# PROC099A_HD_Connector.net
KiCad netlist of a schematic drawn in Altium Designer
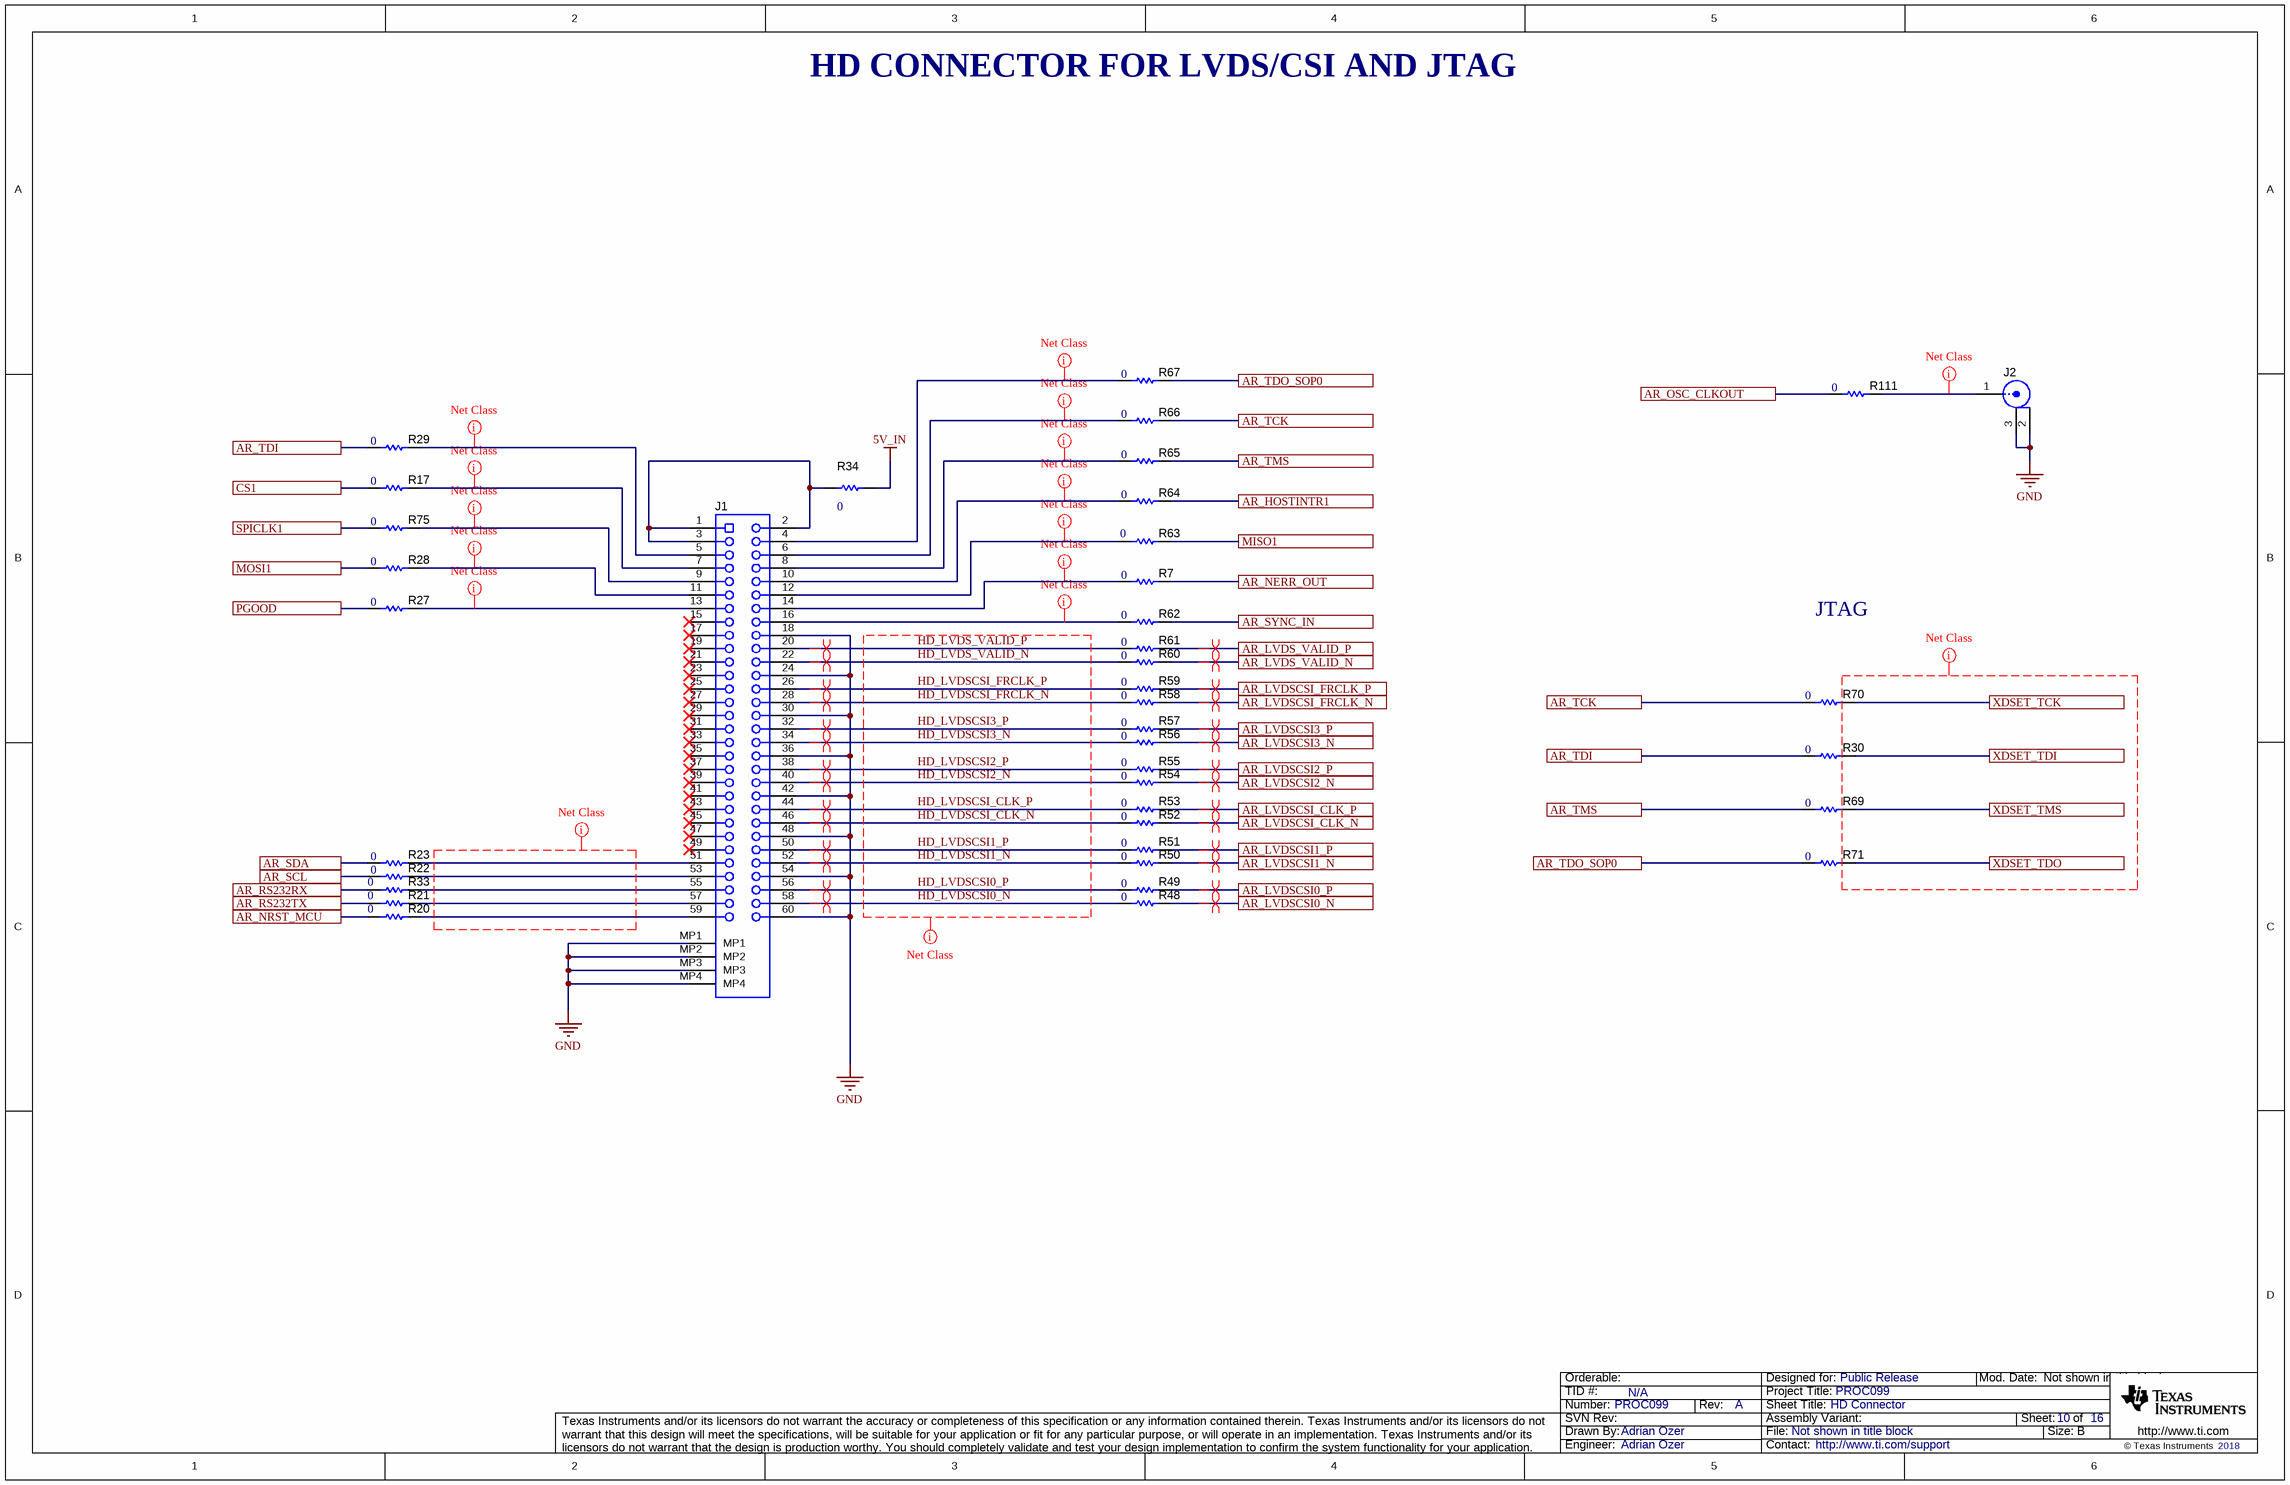
[diagram p0: PROC099A_HD Connector.SchDoc]

(export (version "E")
  (design (tool "Eeschema 10.0.6"))
  (components
    (comp (ref "J1")
      (value "QSH-030-01-L-D-A")
      (footprint "Samtec_QSH-030-01-X-D-A")
      (description "Receptacle, 0.5 mm, 30x2, Gold, TH")
      (fields (field (name "MANUFACTURER") "Samtec") (field (name "PUBLISHER") "Texas Instruments"))
      (libsource (lib "Altium Vault - TI") (part "Receptacle_30x2_4MP_LeftRight"))
    )
    (comp (ref "J2")
      (value "128-0711-201")
      (footprint "Johnson_128-0711-201")
      (description "UMC Straight Jack Receptacle, 50 Ohm, Gold, SMT")
      (fields
        (field (name "MANUFACTURER") "Cinch Connectivity")
        (field (name "PUBLISHER") "Texas Instruments")
      )
      (libsource (lib "Altium Vault - TI") (part "CMP-0055788-1"))
    )
    (comp (ref "R7")
      (value "CRCW02010000Z0ED")
      (footprint "0201_Silk")
      (description "RES, 0, 5%, 0.05 W, 0201")
      (fields (field (name "MANUFACTURER") "Vishay-Dale") (field (name "VALUEDISPLAYED") "0"))
      (libsource (lib "Altium Vault - TI") (part "Resistor"))
    )
    (comp (ref "R17")
      (value "CRCW02010000Z0ED")
      (footprint "0201_Silk")
      (description "RES, 0, 5%, 0.05 W, 0201")
      (fields (field (name "MANUFACTURER") "Vishay-Dale") (field (name "VALUEDISPLAYED") "0"))
      (libsource (lib "Altium Vault - TI") (part "Resistor"))
    )
    (comp (ref "R20")
      (value "CRCW02010000Z0ED")
      (footprint "0201_Silk")
      (description "RES, 0, 5%, 0.05 W, 0201")
      (fields (field (name "MANUFACTURER") "Vishay-Dale") (field (name "VALUEDISPLAYED") "0"))
      (libsource (lib "Altium Vault - TI") (part "Resistor"))
    )
    (comp (ref "R21")
      (value "CRCW02010000Z0ED")
      (footprint "0201_Silk")
      (description "RES, 0, 5%, 0.05 W, 0201")
      (fields (field (name "MANUFACTURER") "Vishay-Dale") (field (name "VALUEDISPLAYED") "0"))
      (libsource (lib "Altium Vault - TI") (part "Resistor"))
    )
    (comp (ref "R22")
      (value "CRCW02010000Z0ED")
      (footprint "0201_Silk")
      (description "RES, 0, 5%, 0.05 W, 0201")
      (fields (field (name "MANUFACTURER") "Vishay-Dale") (field (name "VALUEDISPLAYED") "0"))
      (libsource (lib "Altium Vault - TI") (part "Resistor"))
    )
    (comp (ref "R23")
      (value "CRCW02010000Z0ED")
      (footprint "0201_Silk")
      (description "RES, 0, 5%, 0.05 W, 0201")
      (fields (field (name "MANUFACTURER") "Vishay-Dale") (field (name "VALUEDISPLAYED") "0"))
      (libsource (lib "Altium Vault - TI") (part "Resistor"))
    )
    (comp (ref "R27")
      (value "CRCW02010000Z0ED")
      (footprint "0201_Silk")
      (description "RES, 0, 5%, 0.05 W, 0201")
      (fields (field (name "MANUFACTURER") "Vishay-Dale") (field (name "VALUEDISPLAYED") "0"))
      (libsource (lib "Altium Vault - TI") (part "Resistor"))
    )
    (comp (ref "R28")
      (value "CRCW02010000Z0ED")
      (footprint "0201_Silk")
      (description "RES, 0, 5%, 0.05 W, 0201")
      (fields (field (name "MANUFACTURER") "Vishay-Dale") (field (name "VALUEDISPLAYED") "0"))
      (libsource (lib "Altium Vault - TI") (part "Resistor"))
    )
    (comp (ref "R29")
      (value "CRCW02010000Z0ED")
      (footprint "0201_Silk")
      (description "RES, 0, 5%, 0.05 W, 0201")
      (fields (field (name "MANUFACTURER") "Vishay-Dale") (field (name "VALUEDISPLAYED") "0"))
      (libsource (lib "Altium Vault - TI") (part "Resistor"))
    )
    (comp (ref "R30")
      (value "CRCW02010000Z0ED")
      (footprint "0201_Silk")
      (description "RES, 0, 5%, 0.05 W, 0201")
      (fields (field (name "MANUFACTURER") "Vishay-Dale") (field (name "VALUEDISPLAYED") "0"))
      (libsource (lib "Altium Vault - TI") (part "Resistor"))
    )
    (comp (ref "R33")
      (value "CRCW02010000Z0ED")
      (footprint "0201_Silk")
      (description "RES, 0, 5%, 0.05 W, 0201")
      (fields (field (name "MANUFACTURER") "Vishay-Dale") (field (name "VALUEDISPLAYED") "0"))
      (libsource (lib "Altium Vault - TI") (part "Resistor"))
    )
    (comp (ref "R34")
      (value "CRCW20100000Z0EF")
      (footprint "2010L")
      (description "RES, 0, 5%, 0.75 W, AEC-Q200 Grade 0, 2010")
      (fields (field (name "MANUFACTURER") "Vishay-Dale") (field (name "VALUEDISPLAYED") "0"))
      (libsource (lib "Altium Vault - TI") (part "CMP-0016044-3"))
    )
    (comp (ref "R48")
      (value "CRCW02010000Z0ED")
      (footprint "0201_Silk")
      (description "RES, 0, 5%, 0.05 W, 0201")
      (fields (field (name "MANUFACTURER") "Vishay-Dale") (field (name "VALUEDISPLAYED") "0"))
      (libsource (lib "Altium Vault - TI") (part "Resistor"))
    )
    (comp (ref "R49")
      (value "CRCW02010000Z0ED")
      (footprint "0201_Silk")
      (description "RES, 0, 5%, 0.05 W, 0201")
      (fields (field (name "MANUFACTURER") "Vishay-Dale") (field (name "VALUEDISPLAYED") "0"))
      (libsource (lib "Altium Vault - TI") (part "Resistor"))
    )
    (comp (ref "R50")
      (value "CRCW02010000Z0ED")
      (footprint "0201_Silk")
      (description "RES, 0, 5%, 0.05 W, 0201")
      (fields (field (name "MANUFACTURER") "Vishay-Dale") (field (name "VALUEDISPLAYED") "0"))
      (libsource (lib "Altium Vault - TI") (part "Resistor"))
    )
    (comp (ref "R51")
      (value "CRCW02010000Z0ED")
      (footprint "0201_Silk")
      (description "RES, 0, 5%, 0.05 W, 0201")
      (fields (field (name "MANUFACTURER") "Vishay-Dale") (field (name "VALUEDISPLAYED") "0"))
      (libsource (lib "Altium Vault - TI") (part "Resistor"))
    )
    (comp (ref "R52")
      (value "CRCW02010000Z0ED")
      (footprint "0201_Silk")
      (description "RES, 0, 5%, 0.05 W, 0201")
      (fields (field (name "MANUFACTURER") "Vishay-Dale") (field (name "VALUEDISPLAYED") "0"))
      (libsource (lib "Altium Vault - TI") (part "Resistor"))
    )
    (comp (ref "R53")
      (value "CRCW02010000Z0ED")
      (footprint "0201_Silk")
      (description "RES, 0, 5%, 0.05 W, 0201")
      (fields (field (name "MANUFACTURER") "Vishay-Dale") (field (name "VALUEDISPLAYED") "0"))
      (libsource (lib "Altium Vault - TI") (part "Resistor"))
    )
    (comp (ref "R54")
      (value "CRCW02010000Z0ED")
      (footprint "0201_Silk")
      (description "RES, 0, 5%, 0.05 W, 0201")
      (fields (field (name "MANUFACTURER") "Vishay-Dale") (field (name "VALUEDISPLAYED") "0"))
      (libsource (lib "Altium Vault - TI") (part "Resistor"))
    )
    (comp (ref "R55")
      (value "CRCW02010000Z0ED")
      (footprint "0201_Silk")
      (description "RES, 0, 5%, 0.05 W, 0201")
      (fields (field (name "MANUFACTURER") "Vishay-Dale") (field (name "VALUEDISPLAYED") "0"))
      (libsource (lib "Altium Vault - TI") (part "Resistor"))
    )
    (comp (ref "R56")
      (value "CRCW02010000Z0ED")
      (footprint "0201_Silk")
      (description "RES, 0, 5%, 0.05 W, 0201")
      (fields (field (name "MANUFACTURER") "Vishay-Dale") (field (name "VALUEDISPLAYED") "0"))
      (libsource (lib "Altium Vault - TI") (part "Resistor"))
    )
    (comp (ref "R57")
      (value "CRCW02010000Z0ED")
      (footprint "0201_Silk")
      (description "RES, 0, 5%, 0.05 W, 0201")
      (fields (field (name "MANUFACTURER") "Vishay-Dale") (field (name "VALUEDISPLAYED") "0"))
      (libsource (lib "Altium Vault - TI") (part "Resistor"))
    )
    (comp (ref "R58")
      (value "CRCW02010000Z0ED")
      (footprint "0201_Silk")
      (description "RES, 0, 5%, 0.05 W, 0201")
      (fields (field (name "MANUFACTURER") "Vishay-Dale") (field (name "VALUEDISPLAYED") "0"))
      (libsource (lib "Altium Vault - TI") (part "Resistor"))
    )
    (comp (ref "R59")
      (value "CRCW02010000Z0ED")
      (footprint "0201_Silk")
      (description "RES, 0, 5%, 0.05 W, 0201")
      (fields (field (name "MANUFACTURER") "Vishay-Dale") (field (name "VALUEDISPLAYED") "0"))
      (libsource (lib "Altium Vault - TI") (part "Resistor"))
    )
    (comp (ref "R60")
      (value "CRCW02010000Z0ED")
      (footprint "0201_Silk")
      (description "RES, 0, 5%, 0.05 W, 0201")
      (fields (field (name "MANUFACTURER") "Vishay-Dale") (field (name "VALUEDISPLAYED") "0"))
      (libsource (lib "Altium Vault - TI") (part "Resistor"))
    )
    (comp (ref "R61")
      (value "CRCW02010000Z0ED")
      (footprint "0201_Silk")
      (description "RES, 0, 5%, 0.05 W, 0201")
      (fields (field (name "MANUFACTURER") "Vishay-Dale") (field (name "VALUEDISPLAYED") "0"))
      (libsource (lib "Altium Vault - TI") (part "Resistor"))
    )
    (comp (ref "R62")
      (value "CRCW02010000Z0ED")
      (footprint "0201_Silk")
      (description "RES, 0, 5%, 0.05 W, 0201")
      (fields (field (name "MANUFACTURER") "Vishay-Dale") (field (name "VALUEDISPLAYED") "0"))
      (libsource (lib "Altium Vault - TI") (part "Resistor"))
    )
    (comp (ref "R63")
      (value "CRCW02010000Z0ED")
      (footprint "0201_Silk")
      (description "RES, 0, 5%, 0.05 W, 0201")
      (fields (field (name "MANUFACTURER") "Vishay-Dale") (field (name "VALUEDISPLAYED") "0"))
      (libsource (lib "Altium Vault - TI") (part "Resistor"))
    )
    (comp (ref "R64")
      (value "CRCW02010000Z0ED")
      (footprint "0201_Silk")
      (description "RES, 0, 5%, 0.05 W, 0201")
      (fields (field (name "MANUFACTURER") "Vishay-Dale") (field (name "VALUEDISPLAYED") "0"))
      (libsource (lib "Altium Vault - TI") (part "Resistor"))
    )
    (comp (ref "R65")
      (value "CRCW02010000Z0ED")
      (footprint "0201_Silk")
      (description "RES, 0, 5%, 0.05 W, 0201")
      (fields (field (name "MANUFACTURER") "Vishay-Dale") (field (name "VALUEDISPLAYED") "0"))
      (libsource (lib "Altium Vault - TI") (part "Resistor"))
    )
    (comp (ref "R66")
      (value "CRCW02010000Z0ED")
      (footprint "0201_Silk")
      (description "RES, 0, 5%, 0.05 W, 0201")
      (fields (field (name "MANUFACTURER") "Vishay-Dale") (field (name "VALUEDISPLAYED") "0"))
      (libsource (lib "Altium Vault - TI") (part "Resistor"))
    )
    (comp (ref "R67")
      (value "CRCW02010000Z0ED")
      (footprint "0201_Silk")
      (description "RES, 0, 5%, 0.05 W, 0201")
      (fields (field (name "MANUFACTURER") "Vishay-Dale") (field (name "VALUEDISPLAYED") "0"))
      (libsource (lib "Altium Vault - TI") (part "Resistor"))
    )
    (comp (ref "R69")
      (value "CRCW02010000Z0ED")
      (footprint "0201_Silk")
      (description "RES, 0, 5%, 0.05 W, 0201")
      (fields (field (name "MANUFACTURER") "Vishay-Dale") (field (name "VALUEDISPLAYED") "0"))
      (libsource (lib "Altium Vault - TI") (part "Resistor"))
    )
    (comp (ref "R70")
      (value "CRCW02010000Z0ED")
      (footprint "0201_Silk")
      (description "RES, 0, 5%, 0.05 W, 0201")
      (fields (field (name "MANUFACTURER") "Vishay-Dale") (field (name "VALUEDISPLAYED") "0"))
      (libsource (lib "Altium Vault - TI") (part "Resistor"))
    )
    (comp (ref "R71")
      (value "CRCW02010000Z0ED")
      (footprint "0201_Silk")
      (description "RES, 0, 5%, 0.05 W, 0201")
      (fields (field (name "MANUFACTURER") "Vishay-Dale") (field (name "VALUEDISPLAYED") "0"))
      (libsource (lib "Altium Vault - TI") (part "Resistor"))
    )
    (comp (ref "R75")
      (value "CRCW02010000Z0ED")
      (footprint "0201_Silk")
      (description "RES, 0, 5%, 0.05 W, 0201")
      (fields (field (name "MANUFACTURER") "Vishay-Dale") (field (name "VALUEDISPLAYED") "0"))
      (libsource (lib "Altium Vault - TI") (part "Resistor"))
    )
    (comp (ref "R111")
      (value "CRCW02010000Z0ED")
      (footprint "0201_Silk")
      (description "RES, 0, 5%, 0.05 W, 0201")
      (fields (field (name "MANUFACTURER") "Vishay-Dale") (field (name "VALUEDISPLAYED") "0"))
      (libsource (lib "Altium Vault - TI") (part "Resistor"))
    )
  )
  (nets
    (net (code "1") (name "/AR_HOSTINTR1") (class "Default")
      (node (ref "R64") (pin "2") (pinfunction "2_2") (pintype "passive"))
    )
    (net (code "2") (name "/AR_LVDSCSI0_N") (class "Default")
      (node (ref "R48") (pin "2") (pinfunction "2_2") (pintype "passive"))
    )
    (net (code "3") (name "/AR_LVDSCSI0_P") (class "Default")
      (node (ref "R49") (pin "2") (pinfunction "2_2") (pintype "passive"))
    )
    (net (code "4") (name "/AR_LVDSCSI1_N") (class "Default")
      (node (ref "R50") (pin "2") (pinfunction "2_2") (pintype "passive"))
    )
    (net (code "5") (name "/AR_LVDSCSI1_P") (class "Default")
      (node (ref "R51") (pin "2") (pinfunction "2_2") (pintype "passive"))
    )
    (net (code "6") (name "/AR_LVDSCSI2_N") (class "Default")
      (node (ref "R54") (pin "2") (pinfunction "2_2") (pintype "passive"))
    )
    (net (code "7") (name "/AR_LVDSCSI2_P") (class "Default")
      (node (ref "R55") (pin "2") (pinfunction "2_2") (pintype "passive"))
    )
    (net (code "8") (name "/AR_LVDSCSI3_N") (class "Default")
      (node (ref "R56") (pin "2") (pinfunction "2_2") (pintype "passive"))
    )
    (net (code "9") (name "/AR_LVDSCSI3_P") (class "Default")
      (node (ref "R57") (pin "2") (pinfunction "2_2") (pintype "passive"))
    )
    (net (code "10") (name "/AR_LVDSCSI_CLK_N") (class "Default")
      (node (ref "R52") (pin "2") (pinfunction "2_2") (pintype "passive"))
    )
    (net (code "11") (name "/AR_LVDSCSI_CLK_P") (class "Default")
      (node (ref "R53") (pin "2") (pinfunction "2_2") (pintype "passive"))
    )
    (net (code "12") (name "/AR_LVDSCSI_FRCLK_N") (class "Default")
      (node (ref "R58") (pin "2") (pinfunction "2_2") (pintype "passive"))
    )
    (net (code "13") (name "/AR_LVDSCSI_FRCLK_P") (class "Default")
      (node (ref "R59") (pin "2") (pinfunction "2_2") (pintype "passive"))
    )
    (net (code "14") (name "/AR_LVDS_VALID_N") (class "Default")
      (node (ref "R60") (pin "2") (pinfunction "2_2") (pintype "passive"))
    )
    (net (code "15") (name "/AR_LVDS_VALID_P") (class "Default")
      (node (ref "R61") (pin "2") (pinfunction "2_2") (pintype "passive"))
    )
    (net (code "16") (name "/AR_NERR_OUT") (class "Default")
      (node (ref "R7") (pin "2") (pinfunction "2_2") (pintype "passive"))
    )
    (net (code "17") (name "/AR_NRST_MCU") (class "Default")
      (node (ref "R20") (pin "1") (pinfunction "1_1") (pintype "passive"))
    )
    (net (code "18") (name "/AR_OSC_CLKOUT") (class "Default")
      (node (ref "R111") (pin "1") (pinfunction "1_1") (pintype "passive"))
    )
    (net (code "19") (name "/AR_RS232RX") (class "Default")
      (node (ref "R33") (pin "1") (pinfunction "1_1") (pintype "passive"))
    )
    (net (code "20") (name "/AR_RS232TX") (class "Default")
      (node (ref "R21") (pin "1") (pinfunction "1_1") (pintype "passive"))
    )
    (net (code "21") (name "/AR_SCL") (class "Default")
      (node (ref "R22") (pin "1") (pinfunction "1_1") (pintype "passive"))
    )
    (net (code "22") (name "/AR_SDA") (class "Default")
      (node (ref "R23") (pin "1") (pinfunction "1_1") (pintype "passive"))
    )
    (net (code "23") (name "/AR_SYNC_IN") (class "Default")
      (node (ref "R62") (pin "2") (pinfunction "2_2") (pintype "passive"))
    )
    (net (code "24") (name "/AR_TCK") (class "Default")
      (node (ref "R66") (pin "2") (pinfunction "2_2") (pintype "passive"))
      (node (ref "R70") (pin "1") (pinfunction "1_1") (pintype "passive"))
    )
    (net (code "25") (name "/AR_TDI") (class "Default")
      (node (ref "R29") (pin "1") (pinfunction "1_1") (pintype "passive"))
      (node (ref "R30") (pin "1") (pinfunction "1_1") (pintype "passive"))
    )
    (net (code "26") (name "/AR_TDO_SOP0") (class "Default")
      (node (ref "R67") (pin "2") (pinfunction "2_2") (pintype "passive"))
      (node (ref "R71") (pin "1") (pinfunction "1_1") (pintype "passive"))
    )
    (net (code "27") (name "/AR_TMS") (class "Default")
      (node (ref "R65") (pin "2") (pinfunction "2_2") (pintype "passive"))
      (node (ref "R69") (pin "1") (pinfunction "1_1") (pintype "passive"))
    )
    (net (code "28") (name "/CS1") (class "Default")
      (node (ref "R17") (pin "1") (pinfunction "1_1") (pintype "passive"))
    )
    (net (code "29") (name "/HD_LVDSCSI0_N") (class "Default")
      (node (ref "J1") (pin "58") (pinfunction "58_58") (pintype "passive"))
      (node (ref "R48") (pin "1") (pinfunction "1_1") (pintype "passive"))
    )
    (net (code "30") (name "/HD_LVDSCSI0_P") (class "Default")
      (node (ref "J1") (pin "56") (pinfunction "56_56") (pintype "passive"))
      (node (ref "R49") (pin "1") (pinfunction "1_1") (pintype "passive"))
    )
    (net (code "31") (name "/HD_LVDSCSI1_N") (class "Default")
      (node (ref "J1") (pin "52") (pinfunction "52_52") (pintype "passive"))
      (node (ref "R50") (pin "1") (pinfunction "1_1") (pintype "passive"))
    )
    (net (code "32") (name "/HD_LVDSCSI1_P") (class "Default")
      (node (ref "J1") (pin "50") (pinfunction "50_50") (pintype "passive"))
      (node (ref "R51") (pin "1") (pinfunction "1_1") (pintype "passive"))
    )
    (net (code "33") (name "/HD_LVDSCSI2_N") (class "Default")
      (node (ref "J1") (pin "40") (pinfunction "40_40") (pintype "passive"))
      (node (ref "R54") (pin "1") (pinfunction "1_1") (pintype "passive"))
    )
    (net (code "34") (name "/HD_LVDSCSI2_P") (class "Default")
      (node (ref "J1") (pin "38") (pinfunction "38_38") (pintype "passive"))
      (node (ref "R55") (pin "1") (pinfunction "1_1") (pintype "passive"))
    )
    (net (code "35") (name "/HD_LVDSCSI3_N") (class "Default")
      (node (ref "J1") (pin "34") (pinfunction "34_34") (pintype "passive"))
      (node (ref "R56") (pin "1") (pinfunction "1_1") (pintype "passive"))
    )
    (net (code "36") (name "/HD_LVDSCSI3_P") (class "Default")
      (node (ref "J1") (pin "32") (pinfunction "32_32") (pintype "passive"))
      (node (ref "R57") (pin "1") (pinfunction "1_1") (pintype "passive"))
    )
    (net (code "37") (name "/HD_LVDSCSI_CLK_N") (class "Default")
      (node (ref "J1") (pin "46") (pinfunction "46_46") (pintype "passive"))
      (node (ref "R52") (pin "1") (pinfunction "1_1") (pintype "passive"))
    )
    (net (code "38") (name "/HD_LVDSCSI_CLK_P") (class "Default")
      (node (ref "J1") (pin "44") (pinfunction "44_44") (pintype "passive"))
      (node (ref "R53") (pin "1") (pinfunction "1_1") (pintype "passive"))
    )
    (net (code "39") (name "/HD_LVDSCSI_FRCLK_N") (class "Default")
      (node (ref "J1") (pin "28") (pinfunction "28_28") (pintype "passive"))
      (node (ref "R58") (pin "1") (pinfunction "1_1") (pintype "passive"))
    )
    (net (code "40") (name "/HD_LVDSCSI_FRCLK_P") (class "Default")
      (node (ref "J1") (pin "26") (pinfunction "26_26") (pintype "passive"))
      (node (ref "R59") (pin "1") (pinfunction "1_1") (pintype "passive"))
    )
    (net (code "41") (name "/HD_LVDS_VALID_N") (class "Default")
      (node (ref "J1") (pin "22") (pinfunction "22_22") (pintype "passive"))
      (node (ref "R60") (pin "1") (pinfunction "1_1") (pintype "passive"))
    )
    (net (code "42") (name "/HD_LVDS_VALID_P") (class "Default")
      (node (ref "J1") (pin "20") (pinfunction "20_20") (pintype "passive"))
      (node (ref "R61") (pin "1") (pinfunction "1_1") (pintype "passive"))
    )
    (net (code "43") (name "/MISO1") (class "Default")
      (node (ref "R63") (pin "2") (pinfunction "2_2") (pintype "passive"))
    )
    (net (code "44") (name "/MOSI1") (class "Default")
      (node (ref "R28") (pin "1") (pinfunction "1_1") (pintype "passive"))
    )
    (net (code "45") (name "/PGOOD") (class "Default")
      (node (ref "R27") (pin "1") (pinfunction "1_1") (pintype "passive"))
    )
    (net (code "46") (name "/SPICLK1") (class "Default")
      (node (ref "R75") (pin "1") (pinfunction "1_1") (pintype "passive"))
    )
    (net (code "47") (name "/XDSET_TCK") (class "Default")
      (node (ref "R70") (pin "2") (pinfunction "2_2") (pintype "passive"))
    )
    (net (code "48") (name "/XDSET_TDI") (class "Default")
      (node (ref "R30") (pin "2") (pinfunction "2_2") (pintype "passive"))
    )
    (net (code "49") (name "/XDSET_TDO") (class "Default")
      (node (ref "R71") (pin "2") (pinfunction "2_2") (pintype "passive"))
    )
    (net (code "50") (name "/XDSET_TMS") (class "Default")
      (node (ref "R69") (pin "2") (pinfunction "2_2") (pintype "passive"))
    )
    (net (code "51") (name "5V_IN") (class "Default")
      (node (ref "R34") (pin "2") (pinfunction "2_2") (pintype "passive"))
    )
    (net (code "52") (name "GND") (class "Default")
      (node (ref "J1") (pin "18") (pinfunction "18_18") (pintype "passive"))
      (node (ref "J1") (pin "24") (pinfunction "24_24") (pintype "passive"))
      (node (ref "J1") (pin "30") (pinfunction "30_30") (pintype "passive"))
      (node (ref "J1") (pin "36") (pinfunction "36_36") (pintype "passive"))
      (node (ref "J1") (pin "42") (pinfunction "42_42") (pintype "passive"))
      (node (ref "J1") (pin "48") (pinfunction "48_48") (pintype "passive"))
      (node (ref "J1") (pin "54") (pinfunction "54_54") (pintype "passive"))
      (node (ref "J1") (pin "60") (pinfunction "60_60") (pintype "passive"))
      (node (ref "J1") (pin "MP1") (pinfunction "MP1_MP1") (pintype "passive"))
      (node (ref "J1") (pin "MP2") (pinfunction "MP2_MP2") (pintype "passive"))
      (node (ref "J1") (pin "MP3") (pinfunction "MP3_MP3") (pintype "passive"))
      (node (ref "J1") (pin "MP4") (pinfunction "MP4_MP4") (pintype "passive"))
      (node (ref "J2") (pin "2") (pinfunction "2_2") (pintype "passive"))
      (node (ref "J2") (pin "3") (pinfunction "3_3") (pintype "passive"))
    )
    (net (code "53") (name "Net-(J1-Pad1)") (class "Default")
      (node (ref "J1") (pin "1") (pinfunction "1_1") (pintype "passive"))
      (node (ref "J1") (pin "2") (pinfunction "2_2") (pintype "passive"))
      (node (ref "J1") (pin "3") (pinfunction "3_3") (pintype "passive"))
      (node (ref "R34") (pin "1") (pinfunction "1_1") (pintype "passive"))
    )
    (net (code "54") (name "Net-(J1-Pad4)") (class "Default")
      (node (ref "J1") (pin "4") (pinfunction "4_4") (pintype "passive"))
      (node (ref "R67") (pin "1") (pinfunction "1_1") (pintype "passive"))
    )
    (net (code "55") (name "Net-(J1-Pad5)") (class "Default")
      (node (ref "J1") (pin "5") (pinfunction "5_5") (pintype "passive"))
      (node (ref "R29") (pin "2") (pinfunction "2_2") (pintype "passive"))
    )
    (net (code "56") (name "Net-(J1-Pad6)") (class "Default")
      (node (ref "J1") (pin "6") (pinfunction "6_6") (pintype "passive"))
      (node (ref "R66") (pin "1") (pinfunction "1_1") (pintype "passive"))
    )
    (net (code "57") (name "Net-(J1-Pad7)") (class "Default")
      (node (ref "J1") (pin "7") (pinfunction "7_7") (pintype "passive"))
      (node (ref "R17") (pin "2") (pinfunction "2_2") (pintype "passive"))
    )
    (net (code "58") (name "Net-(J1-Pad8)") (class "Default")
      (node (ref "J1") (pin "8") (pinfunction "8_8") (pintype "passive"))
      (node (ref "R65") (pin "1") (pinfunction "1_1") (pintype "passive"))
    )
    (net (code "59") (name "Net-(J1-Pad9)") (class "Default")
      (node (ref "J1") (pin "9") (pinfunction "9_9") (pintype "passive"))
      (node (ref "R75") (pin "2") (pinfunction "2_2") (pintype "passive"))
    )
    (net (code "60") (name "Net-(J1-Pad10)") (class "Default")
      (node (ref "J1") (pin "10") (pinfunction "10_10") (pintype "passive"))
      (node (ref "R64") (pin "1") (pinfunction "1_1") (pintype "passive"))
    )
    (net (code "61") (name "Net-(J1-Pad11)") (class "Default")
      (node (ref "J1") (pin "11") (pinfunction "11_11") (pintype "passive"))
      (node (ref "R28") (pin "2") (pinfunction "2_2") (pintype "passive"))
    )
    (net (code "62") (name "Net-(J1-Pad12)") (class "Default")
      (node (ref "J1") (pin "12") (pinfunction "12_12") (pintype "passive"))
      (node (ref "R63") (pin "1") (pinfunction "1_1") (pintype "passive"))
    )
    (net (code "63") (name "Net-(J1-Pad13)") (class "Default")
      (node (ref "J1") (pin "13") (pinfunction "13_13") (pintype "passive"))
      (node (ref "R27") (pin "2") (pinfunction "2_2") (pintype "passive"))
    )
    (net (code "64") (name "Net-(J1-Pad14)") (class "Default")
      (node (ref "J1") (pin "14") (pinfunction "14_14") (pintype "passive"))
      (node (ref "R7") (pin "1") (pinfunction "1_1") (pintype "passive"))
    )
    (net (code "65") (name "Net-(J1-Pad16)") (class "Default")
      (node (ref "J1") (pin "16") (pinfunction "16_16") (pintype "passive"))
      (node (ref "R62") (pin "1") (pinfunction "1_1") (pintype "passive"))
    )
    (net (code "66") (name "Net-(J1-Pad51)") (class "Default")
      (node (ref "J1") (pin "51") (pinfunction "51_51") (pintype "passive"))
      (node (ref "R23") (pin "2") (pinfunction "2_2") (pintype "passive"))
    )
    (net (code "67") (name "Net-(J1-Pad53)") (class "Default")
      (node (ref "J1") (pin "53") (pinfunction "53_53") (pintype "passive"))
      (node (ref "R22") (pin "2") (pinfunction "2_2") (pintype "passive"))
    )
    (net (code "68") (name "Net-(J1-Pad55)") (class "Default")
      (node (ref "J1") (pin "55") (pinfunction "55_55") (pintype "passive"))
      (node (ref "R33") (pin "2") (pinfunction "2_2") (pintype "passive"))
    )
    (net (code "69") (name "Net-(J1-Pad57)") (class "Default")
      (node (ref "J1") (pin "57") (pinfunction "57_57") (pintype "passive"))
      (node (ref "R21") (pin "2") (pinfunction "2_2") (pintype "passive"))
    )
    (net (code "70") (name "Net-(J1-Pad59)") (class "Default")
      (node (ref "J1") (pin "59") (pinfunction "59_59") (pintype "passive"))
      (node (ref "R20") (pin "2") (pinfunction "2_2") (pintype "passive"))
    )
    (net (code "71") (name "Net-(J2-Pad1)") (class "Default")
      (node (ref "J2") (pin "1") (pinfunction "1_1") (pintype "passive"))
      (node (ref "R111") (pin "2") (pinfunction "2_2") (pintype "passive"))
    )
    (net (code "72") (name "unconnected-(J1-Pad15)") (class "Default")
      (node (ref "J1") (pin "15") (pinfunction "15_15") (pintype "passive+no_connect"))
    )
    (net (code "73") (name "unconnected-(J1-Pad17)") (class "Default")
      (node (ref "J1") (pin "17") (pinfunction "17_17") (pintype "passive+no_connect"))
    )
    (net (code "74") (name "unconnected-(J1-Pad19)") (class "Default")
      (node (ref "J1") (pin "19") (pinfunction "19_19") (pintype "passive+no_connect"))
    )
    (net (code "75") (name "unconnected-(J1-Pad21)") (class "Default")
      (node (ref "J1") (pin "21") (pinfunction "21_21") (pintype "passive+no_connect"))
    )
    (net (code "76") (name "unconnected-(J1-Pad23)") (class "Default")
      (node (ref "J1") (pin "23") (pinfunction "23_23") (pintype "passive+no_connect"))
    )
    (net (code "77") (name "unconnected-(J1-Pad25)") (class "Default")
      (node (ref "J1") (pin "25") (pinfunction "25_25") (pintype "passive+no_connect"))
    )
    (net (code "78") (name "unconnected-(J1-Pad27)") (class "Default")
      (node (ref "J1") (pin "27") (pinfunction "27_27") (pintype "passive+no_connect"))
    )
    (net (code "79") (name "unconnected-(J1-Pad29)") (class "Default")
      (node (ref "J1") (pin "29") (pinfunction "29_29") (pintype "passive+no_connect"))
    )
    (net (code "80") (name "unconnected-(J1-Pad31)") (class "Default")
      (node (ref "J1") (pin "31") (pinfunction "31_31") (pintype "passive+no_connect"))
    )
    (net (code "81") (name "unconnected-(J1-Pad33)") (class "Default")
      (node (ref "J1") (pin "33") (pinfunction "33_33") (pintype "passive+no_connect"))
    )
    (net (code "82") (name "unconnected-(J1-Pad35)") (class "Default")
      (node (ref "J1") (pin "35") (pinfunction "35_35") (pintype "passive+no_connect"))
    )
    (net (code "83") (name "unconnected-(J1-Pad37)") (class "Default")
      (node (ref "J1") (pin "37") (pinfunction "37_37") (pintype "passive+no_connect"))
    )
    (net (code "84") (name "unconnected-(J1-Pad39)") (class "Default")
      (node (ref "J1") (pin "39") (pinfunction "39_39") (pintype "passive+no_connect"))
    )
    (net (code "85") (name "unconnected-(J1-Pad41)") (class "Default")
      (node (ref "J1") (pin "41") (pinfunction "41_41") (pintype "passive+no_connect"))
    )
    (net (code "86") (name "unconnected-(J1-Pad43)") (class "Default")
      (node (ref "J1") (pin "43") (pinfunction "43_43") (pintype "passive+no_connect"))
    )
    (net (code "87") (name "unconnected-(J1-Pad45)") (class "Default")
      (node (ref "J1") (pin "45") (pinfunction "45_45") (pintype "passive+no_connect"))
    )
    (net (code "88") (name "unconnected-(J1-Pad47)") (class "Default")
      (node (ref "J1") (pin "47") (pinfunction "47_47") (pintype "passive+no_connect"))
    )
    (net (code "89") (name "unconnected-(J1-Pad49)") (class "Default")
      (node (ref "J1") (pin "49") (pinfunction "49_49") (pintype "passive+no_connect"))
    )
  )
)
